# MCU.net
KiCad netlist of a schematic drawn in Altium Designer
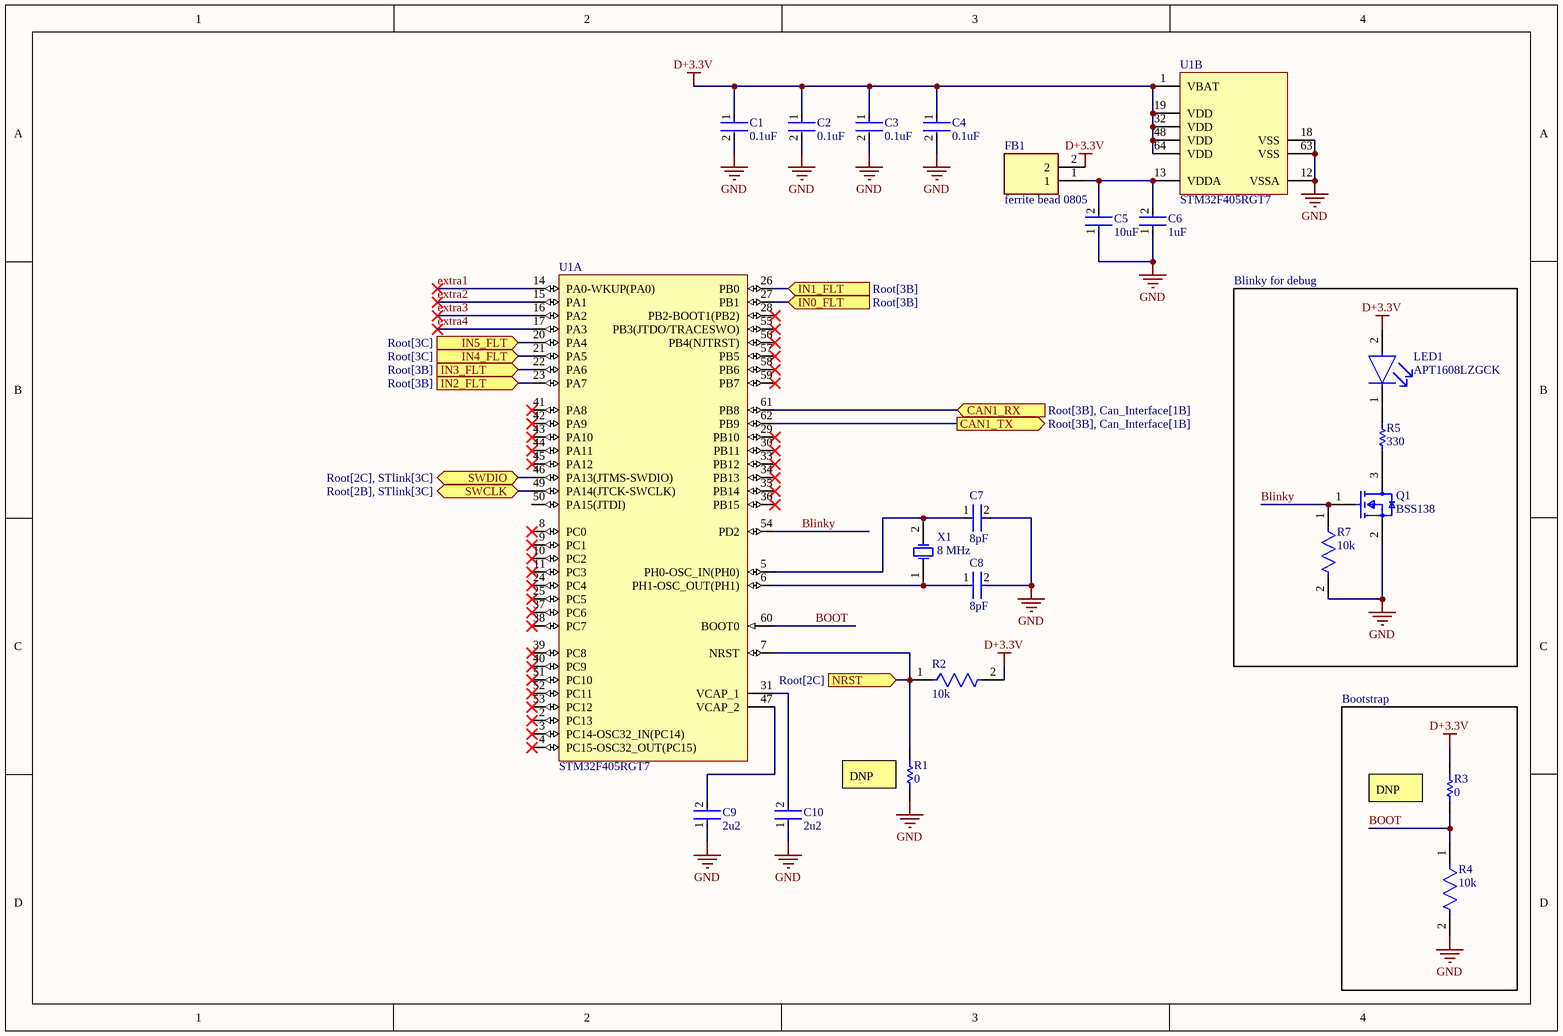
[diagram p0: MCU.SchDoc]

(export (version "E")
  (design (tool "Eeschema 10.0.6"))
  (components
    (comp (ref "C1")
      (value "0.1uF")
      (footprint "FP-CC0603-DA-MFG")
      (description "CAP CER 0.1UF 50V X7R 0603")
      (fields
        (field (name "MANUFACTURER") "YAGEO")
        (field (name "OCTOPART") "https://octopart.com/cc0603mrx7r9bb104-yageo-67308423")
      )
      (libsource (lib "Altium Content Vault") (part "11868f565c42a9108669ba33697ecf6"))
    )
    (comp (ref "C2")
      (value "0.1uF")
      (footprint "FP-CC0603-DA-MFG")
      (description "CAP CER 0.1UF 50V X7R 0603")
      (fields
        (field (name "MANUFACTURER") "YAGEO")
        (field (name "OCTOPART") "https://octopart.com/cc0603mrx7r9bb104-yageo-67308423")
      )
      (libsource (lib "Altium Content Vault") (part "11868f565c42a9108669ba33697ecf6"))
    )
    (comp (ref "C3")
      (value "0.1uF")
      (footprint "FP-CC0603-DA-MFG")
      (description "CAP CER 0.1UF 50V X7R 0603")
      (fields
        (field (name "MANUFACTURER") "YAGEO")
        (field (name "OCTOPART") "https://octopart.com/cc0603mrx7r9bb104-yageo-67308423")
      )
      (libsource (lib "Altium Content Vault") (part "11868f565c42a9108669ba33697ecf6"))
    )
    (comp (ref "C4")
      (value "0.1uF")
      (footprint "FP-CC0603-DA-MFG")
      (description "CAP CER 0.1UF 50V X7R 0603")
      (fields
        (field (name "MANUFACTURER") "YAGEO")
        (field (name "OCTOPART") "https://octopart.com/cc0603mrx7r9bb104-yageo-67308423")
      )
      (libsource (lib "Altium Content Vault") (part "11868f565c42a9108669ba33697ecf6"))
    )
    (comp (ref "C5")
      (value "10uF")
      (footprint "FP-GRM21B-0_2-e0_2_0_7-IPC_C")
      (description "Chip Multilayer Ceramic Capacitors for General Purpose, 0805, 10uF, X7R, 15%, 10%, 16V")
      (libsource (lib "Altium Content Vault") (part "b4654b650e69147ec39a6b967a45e02"))
    )
    (comp (ref "C6")
      (value "1uF")
      (footprint "FP-CC0603-DA-MFG")
      (description "CC0603 1 uF X7R 10.00% 16 V")
      (fields (field (name "MANUFACTURER") "YAGEO") (field (name "TOLERANCE") "0.1"))
      (libsource (lib "Altium Content Vault") (part "11868f565c42a9108669ba33697ecf6"))
    )
    (comp (ref "C7")
      (value "8pF")
      (footprint "FP-C1608-080-0_1-IPC_C")
      (description "Multilayer Ceramic Capacitors 8pF ±0.5pF 50V NP0 SMD 0603")
      (libsource (lib "Altium Content Vault") (part "236180d848d6139a670b325ea6854c9"))
    )
    (comp (ref "C8")
      (value "8pF")
      (footprint "FP-C1608-080-0_1-IPC_C")
      (description "Multilayer Ceramic Capacitors 8pF ±0.5pF 50V NP0 SMD 0603")
      (libsource (lib "Altium Content Vault") (part "236180d848d6139a670b325ea6854c9"))
    )
    (comp (ref "C9")
      (value "2u2")
      (footprint "FP-CC0603-DA-MFG")
      (description "CAP CER 2.2UF 16V X7R 0603")
      (fields (field (name "VOLTAGE") "16 V") (field (name "MANUFACTURER") "YAGEO"))
      (libsource (lib "Altium Content Vault") (part "11868f565c42a9108669ba33697ecf6"))
    )
    (comp (ref "C10")
      (value "2u2")
      (footprint "FP-CC0603-DA-MFG")
      (description "CAP CER 2.2UF 16V X7R 0603")
      (fields (field (name "VOLTAGE") "16 V") (field (name "MANUFACTURER") "YAGEO"))
      (libsource (lib "Altium Content Vault") (part "11868f565c42a9108669ba33697ecf6"))
    )
    (comp (ref "FB1")
      (value "ferrite bead 0805")
      (footprint "FP-RC2012-IPC_A")
      (description "FBMJ2125HS250NT")
      (fields (field (name "MOUSER PART NUMBER") "963-FBMJ2125HS250NT"))
      (libsource (lib "*") (part "FBMJ2125HS250NT"))
    )
    (comp (ref "LED1")
      (value "APT1608LZGCK")
      (footprint "FP-APT1608LZGCK-MFG")
      (description "LED GREEN CLEAR 2SMD")
      (libsource (lib "Altium Content Vault") (part "8706943c75ba83719d021d2fdc84c58"))
    )
    (comp (ref "Q1")
      (value "BSS138")
      (footprint "FP-318-08-IPC_B")
      (description "MOSFET N-CH 50V 220MA SOT-23")
      (libsource (lib "Altium Content Vault") (part "3b9c635fedb024a5347a57b145af9cc"))
    )
    (comp (ref "R1")
      (value "0")
      (footprint "RESC1608X55X25ML10T15")
      (description "Chip Resistor, 0 Ohm, +/- 5%, 0.1 W, -55 to 155 degC, 0603 (1608 Metric), RoHS, Tape and Reel")
      (fields (field (name "TOLERANCE") "5%") (field (name "MANUFACTURER") "Yageo"))
      (libsource (lib "Altium Content Vault") (part "RES-2"))
    )
    (comp (ref "R2")
      (value "10k")
      (footprint "FP-RC0603-0_55-IPC_C")
      (description "RES 10K OHM 1% 1/10W 0603")
      (fields (field (name "TOLERANCE") "1%"))
      (libsource (lib "Altium Content Vault") (part "1029c3af85768c4190bb7ad29bc67b5"))
    )
    (comp (ref "R3")
      (value "0")
      (footprint "RESC1608X55X25ML10T15")
      (description "Chip Resistor, 0 Ohm, +/- 5%, 0.1 W, -55 to 155 degC, 0603 (1608 Metric), RoHS, Tape and Reel")
      (fields (field (name "TOLERANCE") "5%") (field (name "MANUFACTURER") "Yageo"))
      (libsource (lib "Altium Content Vault") (part "RES-2"))
    )
    (comp (ref "R4")
      (value "10k")
      (footprint "FP-RC0603-0_55-IPC_C")
      (description "RES 10K OHM 1% 1/10W 0603")
      (fields (field (name "TOLERANCE") "1%"))
      (libsource (lib "Altium Content Vault") (part "1029c3af85768c4190bb7ad29bc67b5"))
    )
    (comp (ref "R5")
      (value "330")
      (footprint "RESC1608X55X25NL10T15")
      (description "Chip Resistor, 330 Ohm, +/- 1%, 0.1 W, -55 to 155 degC, 0603 (1608 Metric), RoHS, Tape and Reel")
      (fields (field (name "TOLERANCE") "10%"))
      (libsource (lib "Altium Content Vault") (part "RES-2"))
    )
    (comp (ref "R7")
      (value "10k")
      (footprint "FP-RC0603-0_55-IPC_C")
      (description "RES 10K OHM 1% 1/10W 0603")
      (fields (field (name "TOLERANCE") "1%"))
      (libsource (lib "Altium Content Vault") (part "1029c3af85768c4190bb7ad29bc67b5"))
    )
    (comp (ref "U1")
      (value "STM32F405RGT7")
      (footprint "STM-LQFP64_N")
      (fields (field (name "MANUFACTURER") "STMicroelectronics"))
      (libsource (lib "Altium Content Vault") (part "MC-ARM-STM32F4X5-SQ64"))
    )
    (comp (ref "X1")
      (value "8 MHz")
      (footprint "ABRA-ABM3-2_V")
      (description "AA-8.000MALV-T")
      (fields (field (name "MANUFACTURER") "ABRACON") (field (name "TOLERANCE") "20PPM"))
      (libsource (lib "Altium Content Vault") (part "XTAL_1-2-2"))
    )
  )
  (nets
    (net (code "2") (name "/BOOT") (class "Default")
      (node (ref "R3") (pin "2") (pinfunction "2_2") (pintype "passive"))
      (node (ref "R4") (pin "1") (pinfunction "1_1") (pintype "passive"))
      (node (ref "U1") (pin "60") (pinfunction "BOOT0_60") (pintype "input"))
    )
    (net (code "3") (name "/Blinky") (class "Default")
      (node (ref "Q1") (pin "1") (pinfunction "G_1") (pintype "passive"))
      (node (ref "R7") (pin "1") (pinfunction "1_1") (pintype "passive"))
      (node (ref "U1") (pin "54") (pinfunction "PD2_54") (pintype "bidirectional"))
    )
    (net (code "4") (name "/CAN1_RX") (class "Default")
      (node (ref "U1") (pin "61") (pinfunction "PB8_61") (pintype "bidirectional"))
    )
    (net (code "5") (name "/CAN1_TX") (class "Default")
      (node (ref "U1") (pin "62") (pinfunction "PB9_62") (pintype "bidirectional"))
    )
    (net (code "6") (name "/IN0_FLT") (class "Default")
      (node (ref "U1") (pin "27") (pinfunction "PB1_27") (pintype "bidirectional"))
    )
    (net (code "7") (name "/IN1_FLT") (class "Default")
      (node (ref "U1") (pin "26") (pinfunction "PB0_26") (pintype "bidirectional"))
    )
    (net (code "8") (name "/IN2_FLT") (class "Default")
      (node (ref "U1") (pin "23") (pinfunction "PA7_23") (pintype "bidirectional"))
    )
    (net (code "9") (name "/IN3_FLT") (class "Default")
      (node (ref "U1") (pin "22") (pinfunction "PA6_22") (pintype "bidirectional"))
    )
    (net (code "10") (name "/IN4_FLT") (class "Default")
      (node (ref "U1") (pin "21") (pinfunction "PA5_21") (pintype "bidirectional"))
    )
    (net (code "11") (name "/IN5_FLT") (class "Default")
      (node (ref "U1") (pin "20") (pinfunction "PA4_20") (pintype "bidirectional"))
    )
    (net (code "12") (name "/NRST") (class "Default")
      (node (ref "R1") (pin "2") (pinfunction "2_2") (pintype "passive"))
      (node (ref "R2") (pin "1") (pinfunction "1_1") (pintype "passive"))
      (node (ref "U1") (pin "7") (pinfunction "NRST_7") (pintype "bidirectional"))
    )
    (net (code "13") (name "/SWCLK") (class "Default")
      (node (ref "U1") (pin "49") (pinfunction "PA14(JTCK-SWCLK)_49") (pintype "bidirectional"))
    )
    (net (code "14") (name "/SWDIO") (class "Default")
      (node (ref "U1") (pin "46") (pinfunction "PA13(JTMS-SWDIO)_46") (pintype "bidirectional"))
    )
    (net (code "15") (name "/extra1") (class "Default")
      (node (ref "U1") (pin "14") (pinfunction "PA0-WKUP(PA0)_14") (pintype "bidirectional+no_connect"))
    )
    (net (code "16") (name "/extra2") (class "Default")
      (node (ref "U1") (pin "15") (pinfunction "PA1_15") (pintype "bidirectional+no_connect"))
    )
    (net (code "17") (name "/extra3") (class "Default")
      (node (ref "U1") (pin "16") (pinfunction "PA2_16") (pintype "bidirectional+no_connect"))
    )
    (net (code "18") (name "/extra4") (class "Default")
      (node (ref "U1") (pin "17") (pinfunction "PA3_17") (pintype "bidirectional+no_connect"))
    )
    (net (code "19") (name "D+3.3V") (class "Default")
      (node (ref "C1") (pin "1") (pinfunction "1_1") (pintype "passive"))
      (node (ref "C2") (pin "1") (pinfunction "1_1") (pintype "passive"))
      (node (ref "C3") (pin "1") (pinfunction "1_1") (pintype "passive"))
      (node (ref "C4") (pin "1") (pinfunction "1_1") (pintype "passive"))
      (node (ref "FB1") (pin "2") (pinfunction "2_2") (pintype "passive"))
      (node (ref "LED1") (pin "2") (pinfunction "A_2") (pintype "passive"))
      (node (ref "R2") (pin "2") (pinfunction "2_2") (pintype "passive"))
      (node (ref "R3") (pin "1") (pinfunction "1_1") (pintype "passive"))
      (node (ref "U1") (pin "1") (pinfunction "VBAT_1") (pintype "power_in"))
      (node (ref "U1") (pin "19") (pinfunction "VDD_19") (pintype "power_in"))
      (node (ref "U1") (pin "32") (pinfunction "VDD_32") (pintype "power_in"))
      (node (ref "U1") (pin "48") (pinfunction "VDD_48") (pintype "power_in"))
      (node (ref "U1") (pin "64") (pinfunction "VDD_64") (pintype "power_in"))
    )
    (net (code "20") (name "GND") (class "Default")
      (node (ref "C1") (pin "2") (pinfunction "2_2") (pintype "passive"))
      (node (ref "C10") (pin "1") (pinfunction "1_1") (pintype "passive"))
      (node (ref "C2") (pin "2") (pinfunction "2_2") (pintype "passive"))
      (node (ref "C3") (pin "2") (pinfunction "2_2") (pintype "passive"))
      (node (ref "C4") (pin "2") (pinfunction "2_2") (pintype "passive"))
      (node (ref "C5") (pin "1") (pinfunction "1_1") (pintype "passive"))
      (node (ref "C6") (pin "1") (pinfunction "1_1") (pintype "passive"))
      (node (ref "C7") (pin "2") (pinfunction "2_2") (pintype "passive"))
      (node (ref "C8") (pin "2") (pinfunction "2_2") (pintype "passive"))
      (node (ref "C9") (pin "1") (pinfunction "1_1") (pintype "passive"))
      (node (ref "Q1") (pin "2") (pinfunction "S_2") (pintype "passive"))
      (node (ref "R1") (pin "1") (pinfunction "1_1") (pintype "passive"))
      (node (ref "R4") (pin "2") (pinfunction "2_2") (pintype "passive"))
      (node (ref "R7") (pin "2") (pinfunction "2_2") (pintype "passive"))
      (node (ref "U1") (pin "12") (pinfunction "VSSA_12") (pintype "power_in"))
      (node (ref "U1") (pin "18") (pinfunction "VSS_18") (pintype "power_in"))
      (node (ref "U1") (pin "63") (pinfunction "VSS_63") (pintype "power_in"))
    )
    (net (code "21") (name "Net-(LED1-C)") (class "Default")
      (node (ref "LED1") (pin "1") (pinfunction "C_1") (pintype "passive"))
      (node (ref "R5") (pin "2") (pinfunction "2_2") (pintype "passive"))
    )
    (net (code "22") (name "Net-(Q1-D)") (class "Default")
      (node (ref "Q1") (pin "3") (pinfunction "D_3") (pintype "passive"))
      (node (ref "R5") (pin "1") (pinfunction "1_1") (pintype "passive"))
    )
    (net (code "23") (name "Net-(U1A-PH0-OSC_IN(PH0))") (class "Default")
      (node (ref "C7") (pin "1") (pinfunction "1_1") (pintype "passive"))
      (node (ref "U1") (pin "5") (pinfunction "PH0-OSC_IN(PH0)_5") (pintype "bidirectional"))
      (node (ref "X1") (pin "2") (pinfunction "X2_2") (pintype "passive"))
    )
    (net (code "24") (name "Net-(U1A-PH1-OSC_OUT(PH1))") (class "Default")
      (node (ref "C8") (pin "1") (pinfunction "1_1") (pintype "passive"))
      (node (ref "U1") (pin "6") (pinfunction "PH1-OSC_OUT(PH1)_6") (pintype "bidirectional"))
      (node (ref "X1") (pin "1") (pinfunction "X1_1") (pintype "passive"))
    )
    (net (code "25") (name "Net-(U1A-VCAP_1)") (class "Default")
      (node (ref "C10") (pin "2") (pinfunction "2_2") (pintype "passive"))
      (node (ref "U1") (pin "31") (pinfunction "VCAP_1_31") (pintype "power_in"))
    )
    (net (code "26") (name "Net-(U1A-VCAP_2)") (class "Default")
      (node (ref "C9") (pin "2") (pinfunction "2_2") (pintype "passive"))
      (node (ref "U1") (pin "47") (pinfunction "VCAP_2_47") (pintype "power_in"))
    )
    (net (code "27") (name "Net-(U1B-VDDA)") (class "Default")
      (node (ref "C5") (pin "2") (pinfunction "2_2") (pintype "passive"))
      (node (ref "C6") (pin "2") (pinfunction "2_2") (pintype "passive"))
      (node (ref "FB1") (pin "1") (pinfunction "1_1") (pintype "passive"))
      (node (ref "U1") (pin "13") (pinfunction "VDDA_13") (pintype "power_in"))
    )
    (net (code "28") (name "unconnected-(U1A-PA8-Pad41)") (class "Default")
      (node (ref "U1") (pin "41") (pinfunction "PA8_41") (pintype "bidirectional+no_connect"))
    )
    (net (code "29") (name "unconnected-(U1A-PA9-Pad42)") (class "Default")
      (node (ref "U1") (pin "42") (pinfunction "PA9_42") (pintype "bidirectional+no_connect"))
    )
    (net (code "30") (name "unconnected-(U1A-PA10-Pad43)") (class "Default")
      (node (ref "U1") (pin "43") (pinfunction "PA10_43") (pintype "bidirectional+no_connect"))
    )
    (net (code "31") (name "unconnected-(U1A-PA11-Pad44)") (class "Default")
      (node (ref "U1") (pin "44") (pinfunction "PA11_44") (pintype "bidirectional+no_connect"))
    )
    (net (code "32") (name "unconnected-(U1A-PA12-Pad45)") (class "Default")
      (node (ref "U1") (pin "45") (pinfunction "PA12_45") (pintype "bidirectional+no_connect"))
    )
    (net (code "33") (name "unconnected-(U1A-PA15(JTDI)-Pad50)") (class "Default")
      (node (ref "U1") (pin "50") (pinfunction "PA15(JTDI)_50") (pintype "bidirectional"))
    )
    (net (code "34") (name "unconnected-(U1A-PB2-BOOT1(PB2)-Pad28)") (class "Default")
      (node (ref "U1") (pin "28") (pinfunction "PB2-BOOT1(PB2)_28") (pintype "bidirectional+no_connect"))
    )
    (net (code "35") (name "unconnected-(U1A-PB3(JTDO{slash}TRACESWO)-Pad55)") (class "Default")
      (node (ref "U1") (pin "55") (pinfunction "PB3(JTDO/TRACESWO)_55") (pintype "bidirectional+no_connect"))
    )
    (net (code "36") (name "unconnected-(U1A-PB4(NJTRST)-Pad56)") (class "Default")
      (node (ref "U1") (pin "56") (pinfunction "PB4(NJTRST)_56") (pintype "bidirectional+no_connect"))
    )
    (net (code "37") (name "unconnected-(U1A-PB5-Pad57)") (class "Default")
      (node (ref "U1") (pin "57") (pinfunction "PB5_57") (pintype "bidirectional+no_connect"))
    )
    (net (code "38") (name "unconnected-(U1A-PB6-Pad58)") (class "Default")
      (node (ref "U1") (pin "58") (pinfunction "PB6_58") (pintype "bidirectional+no_connect"))
    )
    (net (code "39") (name "unconnected-(U1A-PB7-Pad59)") (class "Default")
      (node (ref "U1") (pin "59") (pinfunction "PB7_59") (pintype "bidirectional+no_connect"))
    )
    (net (code "40") (name "unconnected-(U1A-PB10-Pad29)") (class "Default")
      (node (ref "U1") (pin "29") (pinfunction "PB10_29") (pintype "bidirectional+no_connect"))
    )
    (net (code "41") (name "unconnected-(U1A-PB11-Pad30)") (class "Default")
      (node (ref "U1") (pin "30") (pinfunction "PB11_30") (pintype "bidirectional+no_connect"))
    )
    (net (code "42") (name "unconnected-(U1A-PB12-Pad33)") (class "Default")
      (node (ref "U1") (pin "33") (pinfunction "PB12_33") (pintype "bidirectional+no_connect"))
    )
    (net (code "43") (name "unconnected-(U1A-PB13-Pad34)") (class "Default")
      (node (ref "U1") (pin "34") (pinfunction "PB13_34") (pintype "bidirectional+no_connect"))
    )
    (net (code "44") (name "unconnected-(U1A-PB14-Pad35)") (class "Default")
      (node (ref "U1") (pin "35") (pinfunction "PB14_35") (pintype "bidirectional+no_connect"))
    )
    (net (code "45") (name "unconnected-(U1A-PB15-Pad36)") (class "Default")
      (node (ref "U1") (pin "36") (pinfunction "PB15_36") (pintype "bidirectional+no_connect"))
    )
    (net (code "46") (name "unconnected-(U1A-PC0-Pad8)") (class "Default")
      (node (ref "U1") (pin "8") (pinfunction "PC0_8") (pintype "bidirectional+no_connect"))
    )
    (net (code "47") (name "unconnected-(U1A-PC1-Pad9)") (class "Default")
      (node (ref "U1") (pin "9") (pinfunction "PC1_9") (pintype "bidirectional+no_connect"))
    )
    (net (code "48") (name "unconnected-(U1A-PC2-Pad10)") (class "Default")
      (node (ref "U1") (pin "10") (pinfunction "PC2_10") (pintype "bidirectional+no_connect"))
    )
    (net (code "49") (name "unconnected-(U1A-PC3-Pad11)") (class "Default")
      (node (ref "U1") (pin "11") (pinfunction "PC3_11") (pintype "bidirectional+no_connect"))
    )
    (net (code "50") (name "unconnected-(U1A-PC4-Pad24)") (class "Default")
      (node (ref "U1") (pin "24") (pinfunction "PC4_24") (pintype "bidirectional+no_connect"))
    )
    (net (code "51") (name "unconnected-(U1A-PC5-Pad25)") (class "Default")
      (node (ref "U1") (pin "25") (pinfunction "PC5_25") (pintype "bidirectional+no_connect"))
    )
    (net (code "52") (name "unconnected-(U1A-PC6-Pad37)") (class "Default")
      (node (ref "U1") (pin "37") (pinfunction "PC6_37") (pintype "bidirectional+no_connect"))
    )
    (net (code "53") (name "unconnected-(U1A-PC7-Pad38)") (class "Default")
      (node (ref "U1") (pin "38") (pinfunction "PC7_38") (pintype "bidirectional+no_connect"))
    )
    (net (code "54") (name "unconnected-(U1A-PC8-Pad39)") (class "Default")
      (node (ref "U1") (pin "39") (pinfunction "PC8_39") (pintype "bidirectional+no_connect"))
    )
    (net (code "55") (name "unconnected-(U1A-PC9-Pad40)") (class "Default")
      (node (ref "U1") (pin "40") (pinfunction "PC9_40") (pintype "bidirectional+no_connect"))
    )
    (net (code "56") (name "unconnected-(U1A-PC10-Pad51)") (class "Default")
      (node (ref "U1") (pin "51") (pinfunction "PC10_51") (pintype "bidirectional+no_connect"))
    )
    (net (code "57") (name "unconnected-(U1A-PC11-Pad52)") (class "Default")
      (node (ref "U1") (pin "52") (pinfunction "PC11_52") (pintype "bidirectional+no_connect"))
    )
    (net (code "58") (name "unconnected-(U1A-PC12-Pad53)") (class "Default")
      (node (ref "U1") (pin "53") (pinfunction "PC12_53") (pintype "bidirectional+no_connect"))
    )
    (net (code "59") (name "unconnected-(U1A-PC13-Pad2)") (class "Default")
      (node (ref "U1") (pin "2") (pinfunction "PC13_2") (pintype "bidirectional+no_connect"))
    )
    (net (code "60") (name "unconnected-(U1A-PC14-OSC32_IN(PC14)-Pad3)") (class "Default")
      (node (ref "U1") (pin "3") (pinfunction "PC14-OSC32_IN(PC14)_3") (pintype "bidirectional+no_connect"))
    )
    (net (code "61") (name "unconnected-(U1A-PC15-OSC32_OUT(PC15)-Pad4)") (class "Default")
      (node (ref "U1") (pin "4") (pinfunction "PC15-OSC32_OUT(PC15)_4") (pintype "bidirectional+no_connect"))
    )
  )
)
